# power-eth.net
KiCad netlist of a schematic drawn in Altium Designer
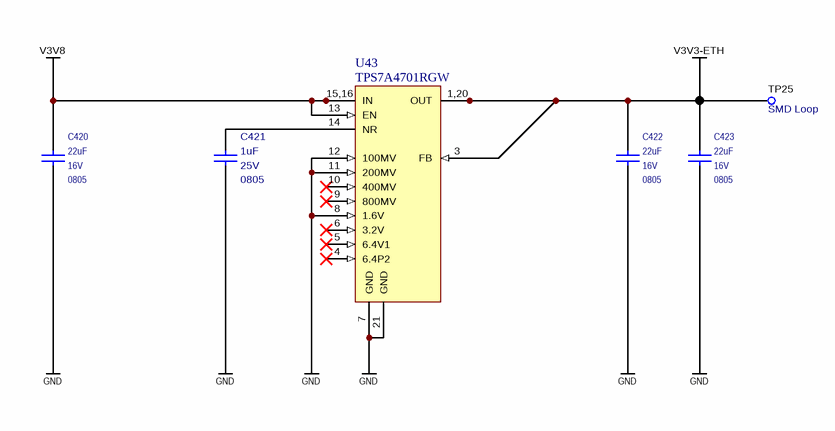
[diagram p0: power-eth.SchDoc]

(export (version "E")
  (design (tool "Eeschema 10.0.6"))
  (components
    (comp (ref "C420")
      (value "22uF")
      (footprint "generic:CAPC200X125X145L45N")
      (description "Ceramic Capacitor 22uF ±20% 16V X5R 0805")
      (fields
        (field (name "MANUFACTURER") "Samsung Electro-Mechanics")
        (field (name "VOLTAGE") "16V")
        (field (name "PACKAGE") "0805")
        (field (name "TOLERANCE") "±20%")
      )
      (libsource (lib "generic") (part "CAP 0603"))
    )
    (comp (ref "C421")
      (value "1uF")
      (footprint "CAPC160X80X90L20N")
      (description "Ceramic Capacitor 1uF ±10% 25V X7R 0805")
      (fields
        (field (name "MANUFACTURER") "Taiyo Yuden")
        (field (name "TOLERANCE") "±10%")
        (field (name "PACKAGE") "0805")
        (field (name "VOLTAGE") "25V")
      )
      (libsource (lib "capacitors") (part "CAP"))
    )
    (comp (ref "C422")
      (value "22uF")
      (footprint "generic:CAPC200X125X145L45N")
      (description "Ceramic Capacitor 22uF ±20% 16V X5R 0805")
      (fields
        (field (name "MANUFACTURER") "Samsung Electro-Mechanics")
        (field (name "VOLTAGE") "16V")
        (field (name "PACKAGE") "0805")
        (field (name "TOLERANCE") "±20%")
      )
      (libsource (lib "generic") (part "CAP 0603"))
    )
    (comp (ref "C423")
      (value "22uF")
      (footprint "generic:CAPC200X125X145L45N")
      (description "Ceramic Capacitor 22uF ±20% 16V X5R 0805")
      (fields
        (field (name "MANUFACTURER") "Samsung Electro-Mechanics")
        (field (name "VOLTAGE") "16V")
        (field (name "PACKAGE") "0805")
        (field (name "TOLERANCE") "±20%")
      )
      (libsource (lib "generic") (part "CAP 0603"))
    )
    (comp (ref "TP25")
      (value "5015")
      (footprint "keystone:5015")
      (description "Test Point SMD")
      (fields (field (name "MANUFACTURER") "Keystone") (field (name "NOTES") "SMD Loop"))
      (libsource (lib "generic") (part "TEST_POINT_SMD_50"))
    )
    (comp (ref "U43")
      (value "TPS7A4701RGW")
      (footprint "QFN65P500X500X100-21N")
      (description "Low-Dropout Linear Regulator 20-VQFN")
      (fields (field (name "MANUFACTURER") "Texas Instruments"))
      (libsource (lib "ti") (part "TPS7A4701RGW_1"))
    )
  )
  (nets
    (net (code "1") (name "GND") (class "Default")
      (node (ref "C420") (pin "1") (pinfunction "1_1") (pintype "passive"))
      (node (ref "C421") (pin "2") (pinfunction "2_2") (pintype "passive"))
      (node (ref "C422") (pin "1") (pinfunction "1_1") (pintype "passive"))
      (node (ref "C423") (pin "1") (pinfunction "1_1") (pintype "passive"))
      (node (ref "U43") (pin "11") (pinfunction "200MV_11") (pintype "input"))
      (node (ref "U43") (pin "12") (pinfunction "100MV_12") (pintype "input"))
      (node (ref "U43") (pin "21") (pinfunction "GND_21") (pintype "power_in"))
      (node (ref "U43") (pin "7") (pinfunction "GND_7") (pintype "power_in"))
      (node (ref "U43") (pin "8") (pinfunction "1.6V_8") (pintype "input"))
    )
    (net (code "2") (name "Net-(U43-NR)") (class "Default")
      (node (ref "C421") (pin "1") (pinfunction "1_1") (pintype "passive"))
      (node (ref "U43") (pin "14") (pinfunction "NR_14") (pintype "passive"))
    )
    (net (code "3") (name "V3V3-ETH") (class "Default")
      (node (ref "C422") (pin "2") (pinfunction "2_2") (pintype "passive"))
      (node (ref "C423") (pin "2") (pinfunction "2_2") (pintype "passive"))
      (node (ref "TP25") (pin "1") (pinfunction "1_1") (pintype "passive"))
      (node (ref "U43") (pin "1") (pinfunction "OUT_1") (pintype "passive"))
      (node (ref "U43") (pin "20") (pinfunction "OUT_20") (pintype "passive"))
      (node (ref "U43") (pin "3") (pinfunction "FB_3") (pintype "input"))
    )
    (net (code "4") (name "V3V8") (class "Default")
      (node (ref "C420") (pin "2") (pinfunction "2_2") (pintype "passive"))
      (node (ref "U43") (pin "13") (pinfunction "EN_13") (pintype "input"))
      (node (ref "U43") (pin "15") (pinfunction "IN_15") (pintype "passive"))
      (node (ref "U43") (pin "16") (pinfunction "IN_16") (pintype "passive"))
    )
    (net (code "5") (name "unconnected-(U43-3.2V-Pad6)") (class "Default")
      (node (ref "U43") (pin "6") (pinfunction "3.2V_6") (pintype "input+no_connect"))
    )
    (net (code "6") (name "unconnected-(U43-6.4P2-Pad4)") (class "Default")
      (node (ref "U43") (pin "4") (pinfunction "6.4P2_4") (pintype "input+no_connect"))
    )
    (net (code "7") (name "unconnected-(U43-6.4V1-Pad5)") (class "Default")
      (node (ref "U43") (pin "5") (pinfunction "6.4V1_5") (pintype "input+no_connect"))
    )
    (net (code "8") (name "unconnected-(U43-400MV-Pad10)") (class "Default")
      (node (ref "U43") (pin "10") (pinfunction "400MV_10") (pintype "input+no_connect"))
    )
    (net (code "9") (name "unconnected-(U43-800MV-Pad9)") (class "Default")
      (node (ref "U43") (pin "9") (pinfunction "800MV_9") (pintype "input+no_connect"))
    )
  )
)
